# amplify.net
KiCad netlist of a schematic drawn in Altium Designer
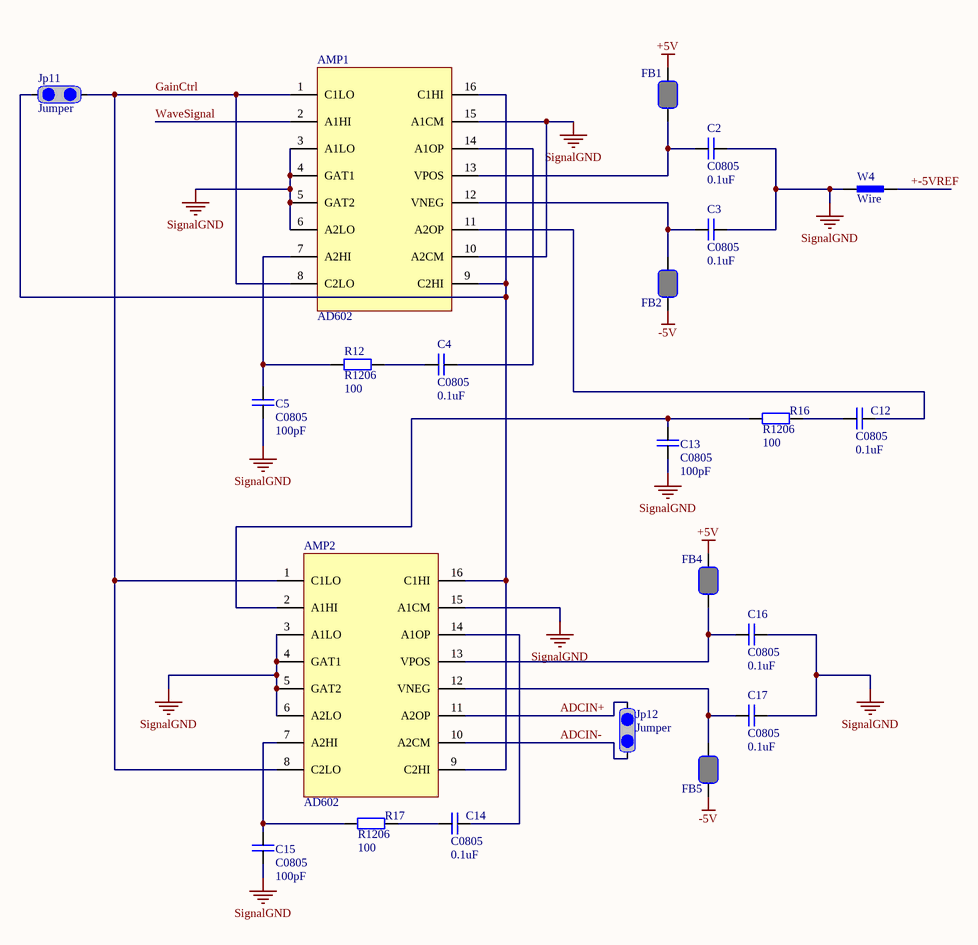
[diagram p0: amplify.SchDoc]

(export (version "E")
  (design (tool "Eeschema 10.0.6"))
  (components
    (comp (ref "AMP1") (value "AD602") (footprint "SOP16") (libsource (lib "UFDLib") (part "AD602")))
    (comp (ref "AMP2") (value "AD602") (footprint "SOP16") (libsource (lib "UFDLib") (part "AD602")))
    (comp (ref "C2")
      (value "C0805")
      (footprint "0805")
      (description "Capacitor, 0805")
      (fields (field (name "ALTIUM_VALUE") "0.1uF"))
      (libsource (lib "UFDLib") (part "C0805"))
    )
    (comp (ref "C3")
      (value "C0805")
      (footprint "0805")
      (description "Capacitor, 0805")
      (fields (field (name "ALTIUM_VALUE") "0.1uF"))
      (libsource (lib "UFDLib") (part "C0805"))
    )
    (comp (ref "C4")
      (value "C0805")
      (footprint "0805")
      (description "Capacitor, 0805")
      (fields (field (name "ALTIUM_VALUE") "0.1uF"))
      (libsource (lib "UFDLib") (part "C0805"))
    )
    (comp (ref "C5")
      (value "C0805")
      (footprint "0805")
      (description "Capacitor, 0805")
      (fields (field (name "ALTIUM_VALUE") "100pF"))
      (libsource (lib "UFDLib") (part "C0805"))
    )
    (comp (ref "C12")
      (value "C0805")
      (footprint "0805")
      (description "Capacitor, 0805")
      (fields (field (name "ALTIUM_VALUE") "0.1uF"))
      (libsource (lib "UFDLib") (part "C0805"))
    )
    (comp (ref "C13")
      (value "C0805")
      (footprint "0805")
      (description "Capacitor, 0805")
      (fields (field (name "ALTIUM_VALUE") "100pF"))
      (libsource (lib "UFDLib") (part "C0805"))
    )
    (comp (ref "C14")
      (value "C0805")
      (footprint "0805")
      (description "Capacitor, 0805")
      (fields (field (name "ALTIUM_VALUE") "0.1uF"))
      (libsource (lib "UFDLib") (part "C0805"))
    )
    (comp (ref "C15")
      (value "C0805")
      (footprint "0805")
      (description "Capacitor, 0805")
      (fields (field (name "ALTIUM_VALUE") "100pF"))
      (libsource (lib "UFDLib") (part "C0805"))
    )
    (comp (ref "C16")
      (value "C0805")
      (footprint "0805")
      (description "Capacitor, 0805")
      (fields (field (name "ALTIUM_VALUE") "0.1uF"))
      (libsource (lib "UFDLib") (part "C0805"))
    )
    (comp (ref "C17")
      (value "C0805")
      (footprint "0805")
      (description "Capacitor, 0805")
      (fields (field (name "ALTIUM_VALUE") "0.1uF"))
      (libsource (lib "UFDLib") (part "C0805"))
    )
    (comp (ref "FB1")
      (value "FB0805")
      (footprint "0805")
      (description "Chip Bead, 0805")
      (libsource (lib "UFDLib") (part "FB0805"))
    )
    (comp (ref "FB2")
      (value "FB0805")
      (footprint "0805")
      (description "Chip Bead, 0805")
      (libsource (lib "UFDLib") (part "FB0805"))
    )
    (comp (ref "FB4")
      (value "FB0805")
      (footprint "0805")
      (description "Chip Bead, 0805")
      (libsource (lib "UFDLib") (part "FB0805"))
    )
    (comp (ref "FB5")
      (value "FB0805")
      (footprint "0805")
      (description "Chip Bead, 0805")
      (libsource (lib "UFDLib") (part "FB0805"))
    )
    (comp (ref "Jp11") (value "Jumper") (footprint "JUMPER") (libsource (lib "UFDLib") (part "Jumper")))
    (comp (ref "Jp12") (value "Jumper") (footprint "JUMPER") (libsource (lib "UFDLib") (part "Jumper")))
    (comp (ref "R12")
      (value "R1206")
      (footprint "1206")
      (description "Resistor, 1206, 1/4W")
      (fields (field (name "ALTIUM_VALUE") "100"))
      (libsource (lib "UFDLib") (part "R1206"))
    )
    (comp (ref "R16")
      (value "R1206")
      (footprint "1206")
      (description "Resistor, 1206, 1/4W")
      (fields (field (name "ALTIUM_VALUE") "100"))
      (libsource (lib "UFDLib") (part "R1206"))
    )
    (comp (ref "R17")
      (value "R1206")
      (footprint "1206")
      (description "Resistor, 1206, 1/4W")
      (fields (field (name "ALTIUM_VALUE") "100"))
      (libsource (lib "UFDLib") (part "R1206"))
    )
    (comp (ref "W4") (value "Wire") (footprint "WIRE") (libsource (lib "UFDLib") (part "Wire")))
  )
  (nets
    (net (code "1") (name "+5V") (class "Default")
      (node (ref "FB1") (pin "2") (pinfunction "b_2") (pintype "passive"))
      (node (ref "FB4") (pin "2") (pinfunction "b_2") (pintype "passive"))
    )
    (net (code "2") (name "-5V") (class "Default")
      (node (ref "FB2") (pin "1") (pinfunction "a_1") (pintype "passive"))
      (node (ref "FB5") (pin "1") (pinfunction "a_1") (pintype "passive"))
    )
    (net (code "3") (name "/+-5VREF") (class "Default")
      (node (ref "W4") (pin "2") (pinfunction "b_2") (pintype "passive"))
    )
    (net (code "4") (name "/ADCIN+") (class "Default")
      (node (ref "AMP2") (pin "11") (pinfunction "A2OP_11") (pintype "passive"))
      (node (ref "Jp12") (pin "2") (pinfunction "b_2") (pintype "passive"))
    )
    (net (code "5") (name "/ADCIN-") (class "Default")
      (node (ref "AMP2") (pin "10") (pinfunction "A2CM_10") (pintype "passive"))
      (node (ref "Jp12") (pin "1") (pinfunction "a_1") (pintype "passive"))
    )
    (net (code "6") (name "/GainCtrl") (class "Default")
      (node (ref "AMP1") (pin "1") (pinfunction "C1LO_1") (pintype "passive"))
      (node (ref "AMP1") (pin "8") (pinfunction "C2LO_8") (pintype "passive"))
      (node (ref "AMP2") (pin "1") (pinfunction "C1LO_1") (pintype "passive"))
      (node (ref "AMP2") (pin "8") (pinfunction "C2LO_8") (pintype "passive"))
      (node (ref "Jp11") (pin "2") (pinfunction "b_2") (pintype "passive"))
    )
    (net (code "7") (name "/WaveSignal") (class "Default")
      (node (ref "AMP1") (pin "2") (pinfunction "A1HI_2") (pintype "passive"))
    )
    (net (code "8") (name "Net-(AMP1-A1OP)") (class "Default")
      (node (ref "AMP1") (pin "14") (pinfunction "A1OP_14") (pintype "passive"))
      (node (ref "C4") (pin "2") (pinfunction "b_2") (pintype "passive"))
    )
    (net (code "9") (name "Net-(AMP1-A2HI)") (class "Default")
      (node (ref "AMP1") (pin "7") (pinfunction "A2HI_7") (pintype "passive"))
      (node (ref "C5") (pin "2") (pinfunction "b_2") (pintype "passive"))
      (node (ref "R12") (pin "1") (pinfunction "a_1") (pintype "passive"))
    )
    (net (code "10") (name "Net-(AMP1-A2OP)") (class "Default")
      (node (ref "AMP1") (pin "11") (pinfunction "A2OP_11") (pintype "passive"))
      (node (ref "C12") (pin "2") (pinfunction "b_2") (pintype "passive"))
    )
    (net (code "11") (name "Net-(AMP1-C1HI)") (class "Default")
      (node (ref "AMP1") (pin "16") (pinfunction "C1HI_16") (pintype "passive"))
      (node (ref "AMP1") (pin "9") (pinfunction "C2HI_9") (pintype "passive"))
      (node (ref "AMP2") (pin "16") (pinfunction "C1HI_16") (pintype "passive"))
      (node (ref "AMP2") (pin "9") (pinfunction "C2HI_9") (pintype "passive"))
      (node (ref "Jp11") (pin "1") (pinfunction "a_1") (pintype "passive"))
    )
    (net (code "12") (name "Net-(AMP1-VNEG)") (class "Default")
      (node (ref "AMP1") (pin "12") (pinfunction "VNEG_12") (pintype "passive"))
      (node (ref "C3") (pin "1") (pinfunction "a_1") (pintype "passive"))
      (node (ref "FB2") (pin "2") (pinfunction "b_2") (pintype "passive"))
    )
    (net (code "13") (name "Net-(AMP1-VPOS)") (class "Default")
      (node (ref "AMP1") (pin "13") (pinfunction "VPOS_13") (pintype "passive"))
      (node (ref "C2") (pin "1") (pinfunction "a_1") (pintype "passive"))
      (node (ref "FB1") (pin "1") (pinfunction "a_1") (pintype "passive"))
    )
    (net (code "14") (name "Net-(AMP2-A1HI)") (class "Default")
      (node (ref "AMP2") (pin "2") (pinfunction "A1HI_2") (pintype "passive"))
      (node (ref "C13") (pin "2") (pinfunction "b_2") (pintype "passive"))
      (node (ref "R16") (pin "1") (pinfunction "a_1") (pintype "passive"))
    )
    (net (code "15") (name "Net-(AMP2-A1OP)") (class "Default")
      (node (ref "AMP2") (pin "14") (pinfunction "A1OP_14") (pintype "passive"))
      (node (ref "C14") (pin "2") (pinfunction "b_2") (pintype "passive"))
    )
    (net (code "16") (name "Net-(AMP2-A2HI)") (class "Default")
      (node (ref "AMP2") (pin "7") (pinfunction "A2HI_7") (pintype "passive"))
      (node (ref "C15") (pin "2") (pinfunction "b_2") (pintype "passive"))
      (node (ref "R17") (pin "1") (pinfunction "a_1") (pintype "passive"))
    )
    (net (code "17") (name "Net-(AMP2-VNEG)") (class "Default")
      (node (ref "AMP2") (pin "12") (pinfunction "VNEG_12") (pintype "passive"))
      (node (ref "C17") (pin "1") (pinfunction "a_1") (pintype "passive"))
      (node (ref "FB5") (pin "2") (pinfunction "b_2") (pintype "passive"))
    )
    (net (code "18") (name "Net-(AMP2-VPOS)") (class "Default")
      (node (ref "AMP2") (pin "13") (pinfunction "VPOS_13") (pintype "passive"))
      (node (ref "C16") (pin "1") (pinfunction "a_1") (pintype "passive"))
      (node (ref "FB4") (pin "1") (pinfunction "a_1") (pintype "passive"))
    )
    (net (code "19") (name "Net-(C4-a)") (class "Default")
      (node (ref "C4") (pin "1") (pinfunction "a_1") (pintype "passive"))
      (node (ref "R12") (pin "2") (pinfunction "b_2") (pintype "passive"))
    )
    (net (code "20") (name "Net-(C12-a)") (class "Default")
      (node (ref "C12") (pin "1") (pinfunction "a_1") (pintype "passive"))
      (node (ref "R16") (pin "2") (pinfunction "b_2") (pintype "passive"))
    )
    (net (code "21") (name "Net-(C14-a)") (class "Default")
      (node (ref "C14") (pin "1") (pinfunction "a_1") (pintype "passive"))
      (node (ref "R17") (pin "2") (pinfunction "b_2") (pintype "passive"))
    )
    (net (code "22") (name "SignalGND") (class "Default")
      (node (ref "AMP1") (pin "10") (pinfunction "A2CM_10") (pintype "passive"))
      (node (ref "AMP1") (pin "15") (pinfunction "A1CM_15") (pintype "passive"))
      (node (ref "AMP1") (pin "3") (pinfunction "A1LO_3") (pintype "passive"))
      (node (ref "AMP1") (pin "4") (pinfunction "GAT1_4") (pintype "passive"))
      (node (ref "AMP1") (pin "5") (pinfunction "GAT2_5") (pintype "passive"))
      (node (ref "AMP1") (pin "6") (pinfunction "A2LO_6") (pintype "passive"))
      (node (ref "AMP2") (pin "15") (pinfunction "A1CM_15") (pintype "passive"))
      (node (ref "AMP2") (pin "3") (pinfunction "A1LO_3") (pintype "passive"))
      (node (ref "AMP2") (pin "4") (pinfunction "GAT1_4") (pintype "passive"))
      (node (ref "AMP2") (pin "5") (pinfunction "GAT2_5") (pintype "passive"))
      (node (ref "AMP2") (pin "6") (pinfunction "A2LO_6") (pintype "passive"))
      (node (ref "C13") (pin "1") (pinfunction "a_1") (pintype "passive"))
      (node (ref "C15") (pin "1") (pinfunction "a_1") (pintype "passive"))
      (node (ref "C16") (pin "2") (pinfunction "b_2") (pintype "passive"))
      (node (ref "C17") (pin "2") (pinfunction "b_2") (pintype "passive"))
      (node (ref "C2") (pin "2") (pinfunction "b_2") (pintype "passive"))
      (node (ref "C3") (pin "2") (pinfunction "b_2") (pintype "passive"))
      (node (ref "C5") (pin "1") (pinfunction "a_1") (pintype "passive"))
      (node (ref "W4") (pin "1") (pinfunction "a_1") (pintype "passive"))
    )
  )
)
